# 05io.net
KiCad netlist of a schematic drawn in Altium Designer
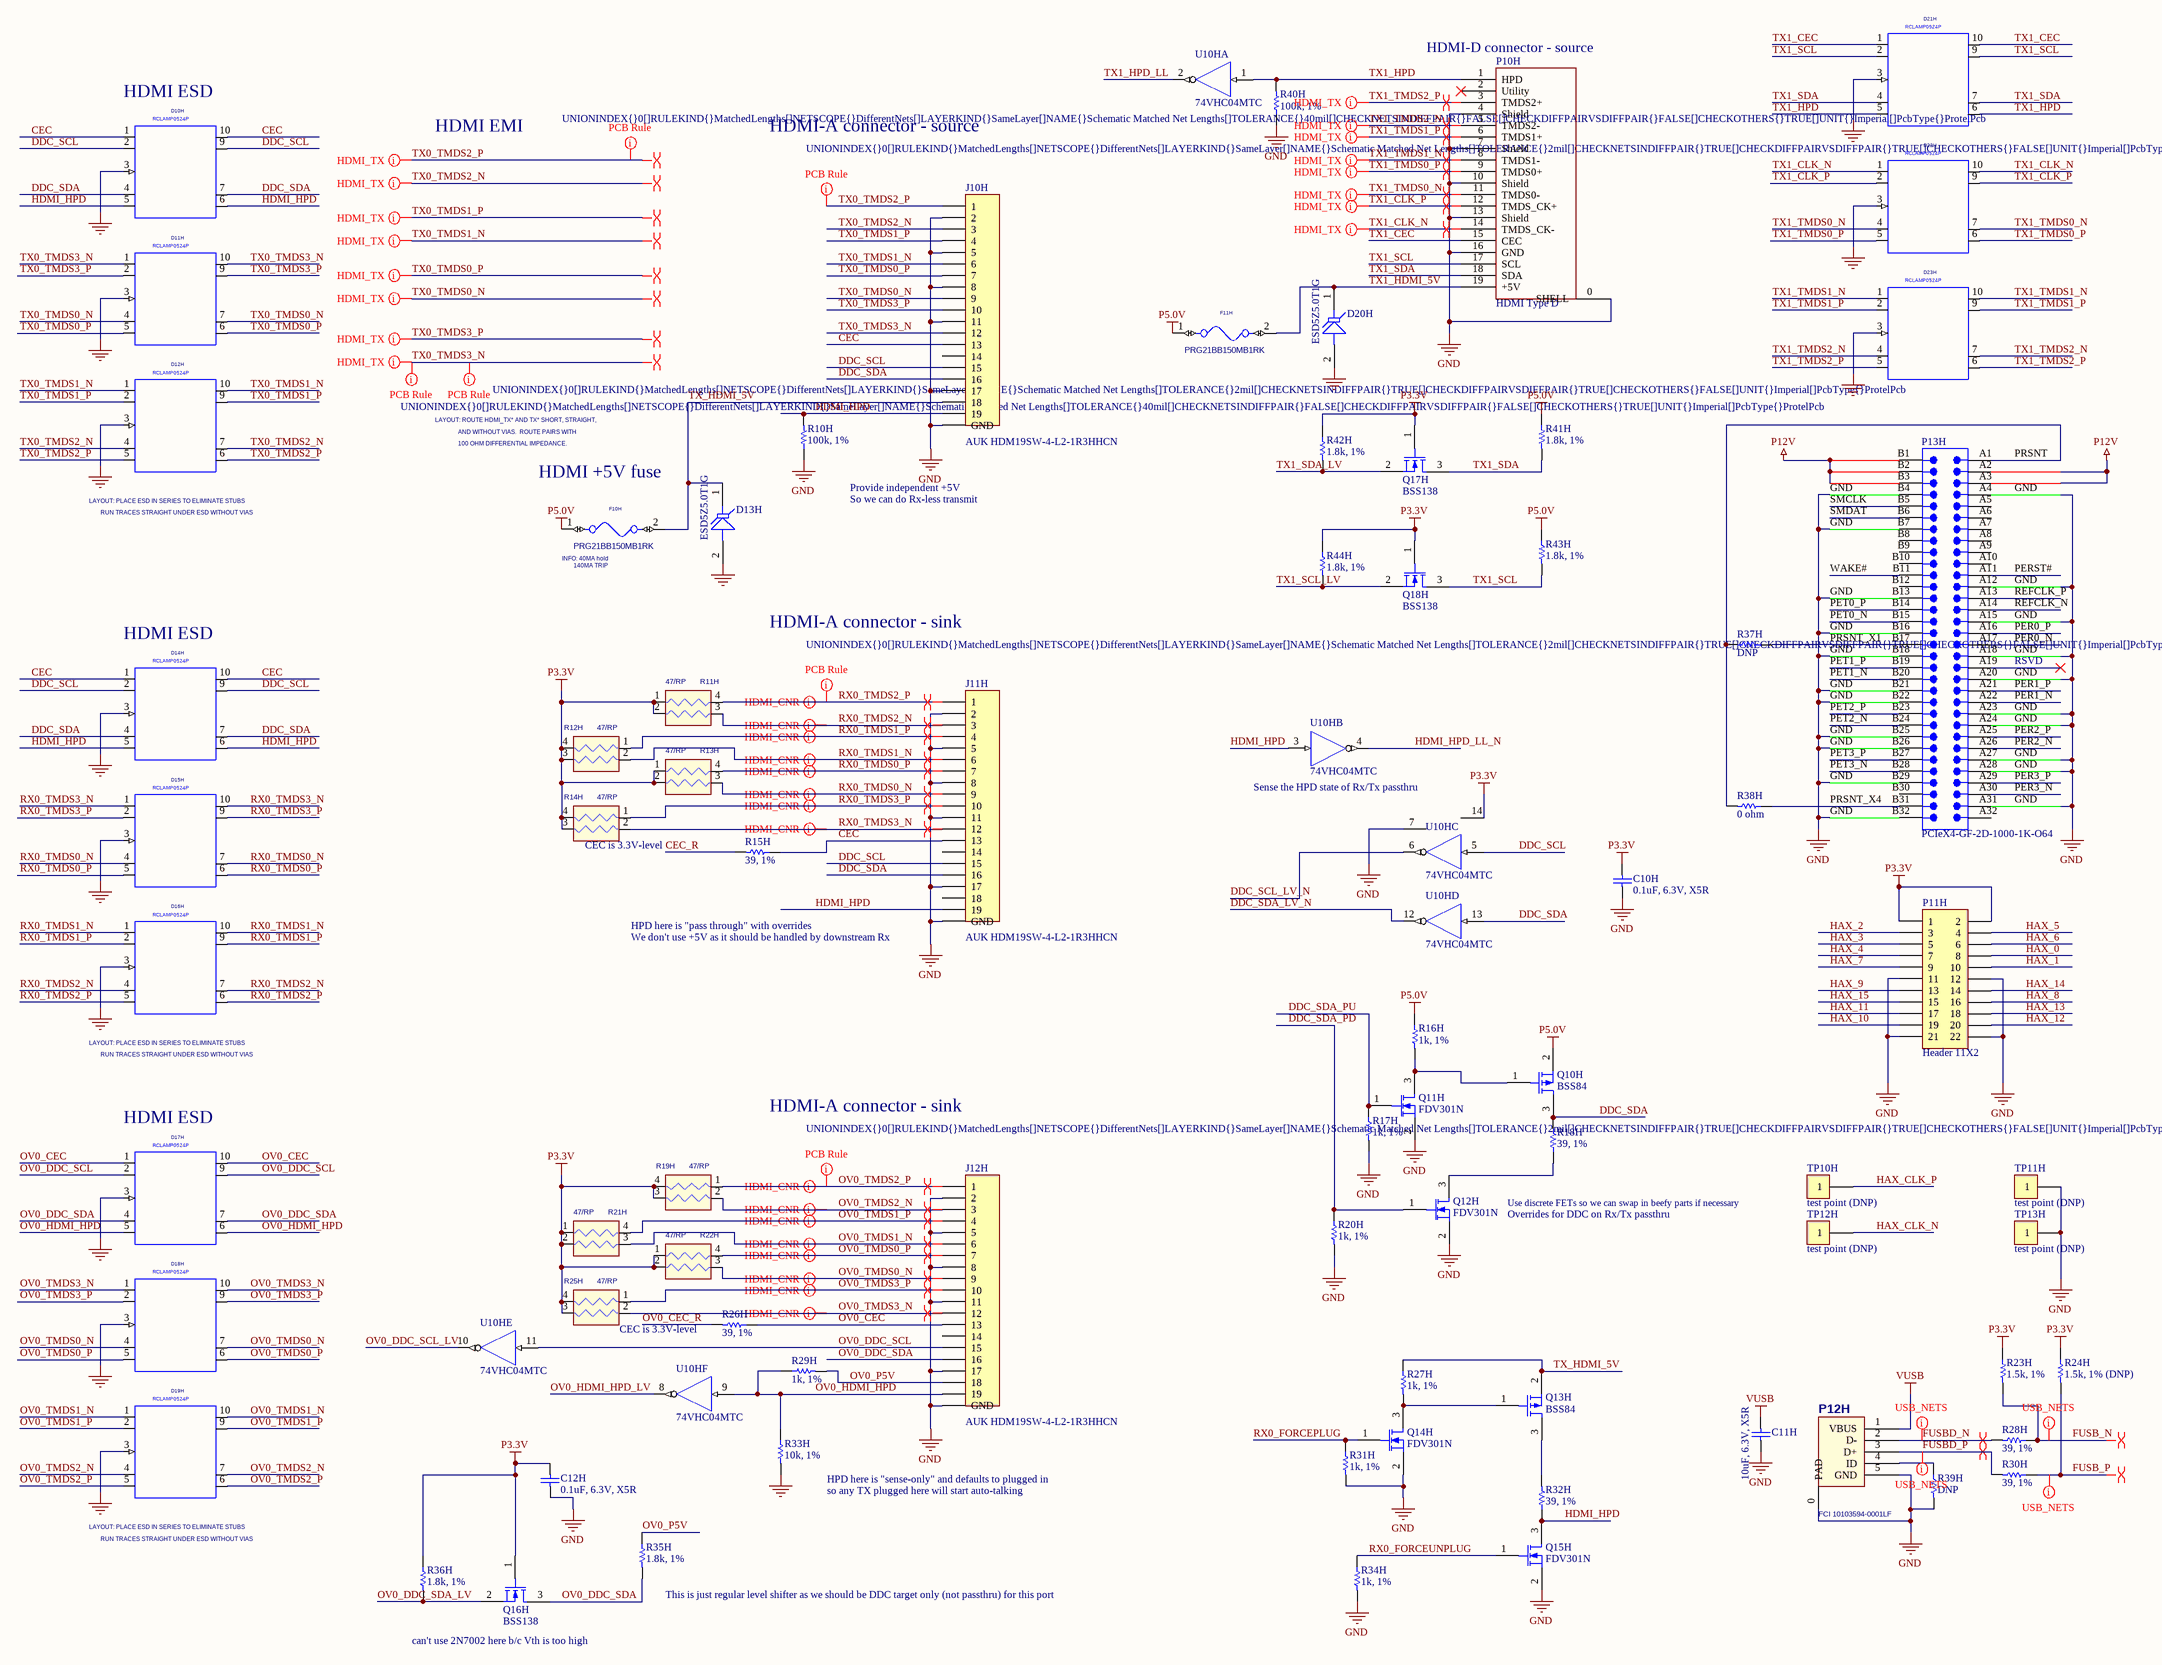
[diagram p0: 05io.SchDoc]

(export (version "E")
  (design (tool "Eeschema 10.0.6"))
  (components
    (comp (ref "C10H")
      (value "0.1uF, 6.3V, X5R")
      (footprint "CAPC0603X03L")
      (description "Capacitor (Semiconductor SIM Model)")
      (fields (field (name "MPN") "CL03A104KQ3NNNC"))
      (libsource (lib "Miscellaneous Devices") (part "Cap Semi"))
    )
    (comp (ref "C11H")
      (value "10uF, 6.3V, X5R")
      (footprint "CAPC1608N")
      (description "Capacitor (Semiconductor SIM Model)")
      (fields (field (name "MPN") "CL10A106MQ8NNNC"))
      (libsource (lib "Miscellaneous Devices") (part "Cap Semi"))
    )
    (comp (ref "C12H")
      (value "0.1uF, 6.3V, X5R")
      (footprint "CAPC0603X03L")
      (description "Capacitor (Semiconductor SIM Model)")
      (fields (field (name "MPN") "CL03A104KQ3NNNC"))
      (libsource (lib "Miscellaneous Devices") (part "Cap Semi"))
    )
    (comp (ref "D10H")
      (value "RCLAMP0524P")
      (fields (field (name "PART_NUMBER") "V00004-001") (field (name "MPN") "RCLAMP0524PATCT"))
      (libsource (lib "*") (part "RCLAMP0524P"))
    )
    (comp (ref "D11H")
      (value "RCLAMP0524P")
      (fields (field (name "PART_NUMBER") "V00004-001") (field (name "MPN") "RCLAMP0524PATCT"))
      (libsource (lib "*") (part "RCLAMP0524P"))
    )
    (comp (ref "D12H")
      (value "RCLAMP0524P")
      (fields (field (name "PART_NUMBER") "V00004-001") (field (name "MPN") "RCLAMP0524PATCT"))
      (libsource (lib "*") (part "RCLAMP0524P"))
    )
    (comp (ref "D13H")
      (value "ESD5Z5.0T1G")
      (footprint "SOD-523")
      (description "On Semi 5.0V standoff TVS diode")
      (fields (field (name "PUBLISHER") "Altium Limited"))
      (libsource (lib "Miscellaneous Devices") (part "Tranzorb"))
    )
    (comp (ref "D14H")
      (value "RCLAMP0524P")
      (fields (field (name "PART_NUMBER") "V00004-001") (field (name "MPN") "RCLAMP0524PATCT"))
      (libsource (lib "*") (part "RCLAMP0524P"))
    )
    (comp (ref "D15H")
      (value "RCLAMP0524P")
      (fields (field (name "PART_NUMBER") "V00004-001") (field (name "MPN") "RCLAMP0524PATCT"))
      (libsource (lib "*") (part "RCLAMP0524P"))
    )
    (comp (ref "D16H")
      (value "RCLAMP0524P")
      (fields (field (name "PART_NUMBER") "V00004-001") (field (name "MPN") "RCLAMP0524PATCT"))
      (libsource (lib "*") (part "RCLAMP0524P"))
    )
    (comp (ref "D17H")
      (value "RCLAMP0524P")
      (fields (field (name "PART_NUMBER") "V00004-001") (field (name "MPN") "RCLAMP0524PATCT"))
      (libsource (lib "*") (part "RCLAMP0524P"))
    )
    (comp (ref "D18H")
      (value "RCLAMP0524P")
      (fields (field (name "PART_NUMBER") "V00004-001") (field (name "MPN") "RCLAMP0524PATCT"))
      (libsource (lib "*") (part "RCLAMP0524P"))
    )
    (comp (ref "D19H")
      (value "RCLAMP0524P")
      (fields (field (name "PART_NUMBER") "V00004-001") (field (name "MPN") "RCLAMP0524PATCT"))
      (libsource (lib "*") (part "RCLAMP0524P"))
    )
    (comp (ref "D20H")
      (value "ESD5Z5.0T1G")
      (footprint "SOD-523")
      (description "On Semi 5.0V standoff TVS diode")
      (fields (field (name "PUBLISHER") "Altium Limited"))
      (libsource (lib "Miscellaneous Devices") (part "Tranzorb"))
    )
    (comp (ref "D21H")
      (value "RCLAMP0524P")
      (fields (field (name "PART_NUMBER") "V00004-001") (field (name "MPN") "RCLAMP0524PATCT"))
      (libsource (lib "*") (part "RCLAMP0524P"))
    )
    (comp (ref "D22H")
      (value "RCLAMP0524P")
      (fields (field (name "PART_NUMBER") "V00004-001") (field (name "MPN") "RCLAMP0524PATCT"))
      (libsource (lib "*") (part "RCLAMP0524P"))
    )
    (comp (ref "D23H")
      (value "RCLAMP0524P")
      (fields (field (name "PART_NUMBER") "V00004-001") (field (name "MPN") "RCLAMP0524PATCT"))
      (libsource (lib "*") (part "RCLAMP0524P"))
    )
    (comp (ref "F10H")
      (value "PRG21BB150MB1RK")
      (description "Murata 140mA fuse, 40mA hold")
      (fields (field (name "PART_NUMBER") "M00014-001"))
      (libsource (lib "*") (part "FUSE0805"))
    )
    (comp (ref "F11H")
      (value "PRG21BB150MB1RK")
      (description "Murata 140mA fuse, 40mA hold")
      (fields (field (name "PART_NUMBER") "M00014-001"))
      (libsource (lib "*") (part "FUSE0805"))
    )
    (comp (ref "J10H")
      (value "AUK HDM19SW-4-L2-1R3HHCN")
      (footprint "MOLEX_47151-0001")
      (description "Molex HDMI connector, Type A")
      (fields (field (name "MPN") "HDM19SW-4-L2-1R3HHCN") (field (name "PUBLISHER") "Altium Limited"))
      (libsource (lib "Miscellaneous Connectors") (part "Header 19"))
    )
    (comp (ref "J11H")
      (value "AUK HDM19SW-4-L2-1R3HHCN")
      (footprint "MOLEX_47151-0001")
      (description "Molex HDMI connector, Type A")
      (fields (field (name "MPN") "HDM19SW-4-L2-1R3HHCN") (field (name "PUBLISHER") "Altium Limited"))
      (libsource (lib "Miscellaneous Connectors") (part "Header 19"))
    )
    (comp (ref "J12H")
      (value "AUK HDM19SW-4-L2-1R3HHCN")
      (footprint "MOLEX_47151-0001")
      (description "Molex HDMI connector, Type A")
      (fields (field (name "MPN") "HDM19SW-4-L2-1R3HHCN") (field (name "PUBLISHER") "Altium Limited"))
      (libsource (lib "Miscellaneous Connectors") (part "Header 19"))
    )
    (comp (ref "P10H")
      (value "HDMI Type D")
      (footprint "MOLEX_0467651301")
      (description "HDMI Type D with through-hole mounts")
      (fields (field (name "MPN") "0467651301"))
      (libsource (lib "commonsch-new") (part "HDMI-TYPE-D"))
    )
    (comp (ref "P11H")
      (value "Header 11X2")
      (footprint "HDR2X11")
      (description "Header, 11-Pin, Dual row")
      (fields (field (name "PUBLISHER") "Altium Limited"))
      (libsource (lib "Miscellaneous Connectors") (part "Header 11X2"))
    )
    (comp (ref "P12H")
      (value "FCI 10103594-0001LF")
      (footprint "USB_MICRO_B_SMT")
      (description "Micro USB B type connector")
      (fields (field (name "MPN") "10103594-0001LF"))
      (libsource (lib "*") (part "USB_MINI-AB_1"))
    )
    (comp (ref "P13H")
      (value "PCIeX4-GF-2D-1000-1K-O64")
      (footprint "PCIeX4-GF-2D-1000-1K-O64")
      (description "Golden finger, PCIeX4, Dual, Opposite, Pitch 1mm, 64-Position")
      (fields (field (name "PUBLISHER") "Altium"))
      (libsource (lib "altium-import") (part "root_3_CMP-0001-00031-1_"))
    )
    (comp (ref "Q10H")
      (value "BSS84")
      (footprint "SOT23-3N")
      (description "P-Channel MOSFET")
      (fields (field (name "PUBLISHER") "Altium Limited"))
      (libsource (lib "Miscellaneous Devices") (part "MOSFET-P"))
    )
    (comp (ref "Q11H")
      (value "FDV301N")
      (footprint "SOT23-3N")
      (description "N-Channel MOSFET")
      (fields (field (name "PUBLISHER") "Altium Limited"))
      (libsource (lib "Miscellaneous Devices") (part "MOSFET-N"))
    )
    (comp (ref "Q12H")
      (value "FDV301N")
      (footprint "SOT23-3N")
      (description "N-Channel MOSFET")
      (fields (field (name "PUBLISHER") "Altium Limited"))
      (libsource (lib "Miscellaneous Devices") (part "MOSFET-N"))
    )
    (comp (ref "Q13H")
      (value "BSS84")
      (footprint "SOT23-3N")
      (description "P-Channel MOSFET")
      (fields (field (name "PUBLISHER") "Altium Limited"))
      (libsource (lib "Miscellaneous Devices") (part "MOSFET-P"))
    )
    (comp (ref "Q14H")
      (value "FDV301N")
      (footprint "SOT23-3N")
      (description "N-Channel MOSFET")
      (fields (field (name "PUBLISHER") "Altium Limited"))
      (libsource (lib "Miscellaneous Devices") (part "MOSFET-N"))
    )
    (comp (ref "Q15H")
      (value "FDV301N")
      (footprint "SOT23-3N")
      (description "N-Channel MOSFET")
      (fields (field (name "PUBLISHER") "Altium Limited"))
      (libsource (lib "Miscellaneous Devices") (part "MOSFET-N"))
    )
    (comp (ref "Q16H")
      (value "BSS138")
      (footprint "SOT23-3N")
      (description "N-Channel MOSFET")
      (fields (field (name "MPN") "BSS138LT1G") (field (name "PUBLISHER") "Altium Limited"))
      (libsource (lib "Miscellaneous Devices") (part "MOSFET-N"))
    )
    (comp (ref "Q17H")
      (value "BSS138")
      (footprint "SOT23-3N")
      (description "N-Channel MOSFET")
      (fields (field (name "MPN") "BSS138LT1G") (field (name "PUBLISHER") "Altium Limited"))
      (libsource (lib "Miscellaneous Devices") (part "MOSFET-N"))
    )
    (comp (ref "Q18H")
      (value "BSS138")
      (footprint "SOT23-3N")
      (description "N-Channel MOSFET")
      (fields (field (name "MPN") "BSS138LT1G") (field (name "PUBLISHER") "Altium Limited"))
      (libsource (lib "Miscellaneous Devices") (part "MOSFET-N"))
    )
    (comp (ref "R10H")
      (value "100k, 1%")
      (footprint "RESC1005N")
      (description "Resistor")
      (fields (field (name "MPN") "ANY"))
      (libsource (lib "Miscellaneous Devices") (part "Res1"))
    )
    (comp (ref "R11H")
      (value "47/RP")
      (fields (field (name "MPN") "RP102PJ470CS") (field (name "MFG") "SAMSUNG"))
      (libsource (lib "") (part "RPACK2_1"))
    )
    (comp (ref "R12H")
      (value "47/RP")
      (fields (field (name "MPN") "RP102PJ470CS") (field (name "MFG") "SAMSUNG"))
      (libsource (lib "*") (part "RPACK2"))
    )
    (comp (ref "R13H")
      (value "47/RP")
      (fields (field (name "MPN") "RP102PJ470CS") (field (name "MFG") "SAMSUNG"))
      (libsource (lib "") (part "RPACK2_1"))
    )
    (comp (ref "R14H")
      (value "47/RP")
      (fields (field (name "MPN") "RP102PJ470CS") (field (name "MFG") "SAMSUNG"))
      (libsource (lib "*") (part "RPACK2"))
    )
    (comp (ref "R15H")
      (value "39, 1%")
      (footprint "RESC1005N")
      (description "Resistor")
      (fields (field (name "MPN") "ANY"))
      (libsource (lib "Miscellaneous Devices") (part "Res1"))
    )
    (comp (ref "R16H")
      (value "1k, 1%")
      (footprint "RESC1005N")
      (description "Resistor")
      (fields (field (name "MPN") "RS02U102FT"))
      (libsource (lib "Miscellaneous Devices") (part "Res1"))
    )
    (comp (ref "R17H")
      (value "1k, 1%")
      (footprint "RESC1005N")
      (description "Resistor")
      (fields (field (name "MPN") "RS02U102FT"))
      (libsource (lib "Miscellaneous Devices") (part "Res1"))
    )
    (comp (ref "R18H")
      (value "39, 1%")
      (footprint "RESC1005N")
      (description "Resistor")
      (fields (field (name "MPN") "ANY"))
      (libsource (lib "Miscellaneous Devices") (part "Res1"))
    )
    (comp (ref "R19H")
      (value "47/RP")
      (fields (field (name "MPN") "RP102PJ470CS") (field (name "MFG") "SAMSUNG"))
      (libsource (lib "*") (part "RPACK2"))
    )
    (comp (ref "R20H")
      (value "1k, 1%")
      (footprint "RESC1005N")
      (description "Resistor")
      (fields (field (name "MPN") "RS02U102FT"))
      (libsource (lib "Miscellaneous Devices") (part "Res1"))
    )
    (comp (ref "R21H")
      (value "47/RP")
      (fields (field (name "MPN") "RP102PJ470CS") (field (name "MFG") "SAMSUNG"))
      (libsource (lib "") (part "RPACK2_1"))
    )
    (comp (ref "R22H")
      (value "47/RP")
      (fields (field (name "MPN") "RP102PJ470CS") (field (name "MFG") "SAMSUNG"))
      (libsource (lib "") (part "RPACK2_1"))
    )
    (comp (ref "R23H")
      (value "1.5k, 1%")
      (footprint "RESC1005N")
      (description "Resistor")
      (fields (field (name "MPN") "RS02U152FT"))
      (libsource (lib "Miscellaneous Devices") (part "Res1"))
    )
    (comp (ref "R24H")
      (value "1.5k, 1% (DNP)")
      (footprint "RESC1005N")
      (description "Resistor")
      (fields (field (name "MPN") "DNP"))
      (libsource (lib "Miscellaneous Devices") (part "Res1"))
    )
    (comp (ref "R25H")
      (value "47/RP")
      (fields (field (name "MPN") "RP102PJ470CS") (field (name "MFG") "SAMSUNG"))
      (libsource (lib "*") (part "RPACK2"))
    )
    (comp (ref "R26H")
      (value "39, 1%")
      (footprint "RESC1005N")
      (description "Resistor")
      (fields (field (name "MPN") "ANY"))
      (libsource (lib "Miscellaneous Devices") (part "Res1"))
    )
    (comp (ref "R27H")
      (value "1k, 1%")
      (footprint "RESC1005N")
      (description "Resistor")
      (fields (field (name "MPN") "RS02U102FT"))
      (libsource (lib "Miscellaneous Devices") (part "Res1"))
    )
    (comp (ref "R28H")
      (value "39, 1%")
      (footprint "RESC1005N")
      (description "Resistor")
      (fields (field (name "MPN") "ANY"))
      (libsource (lib "Miscellaneous Devices") (part "Res1"))
    )
    (comp (ref "R29H")
      (value "1k, 1%")
      (footprint "RESC1005N")
      (description "Resistor")
      (fields (field (name "MPN") "RS02U102FT"))
      (libsource (lib "Miscellaneous Devices") (part "Res1"))
    )
    (comp (ref "R30H")
      (value "39, 1%")
      (footprint "RESC1005N")
      (description "Resistor")
      (fields (field (name "MPN") "ANY"))
      (libsource (lib "Miscellaneous Devices") (part "Res1"))
    )
    (comp (ref "R31H")
      (value "1k, 1%")
      (footprint "RESC1005N")
      (description "Resistor")
      (fields (field (name "MPN") "RS02U102FT"))
      (libsource (lib "Miscellaneous Devices") (part "Res1"))
    )
    (comp (ref "R32H")
      (value "39, 1%")
      (footprint "RESC1005N")
      (description "Resistor")
      (fields (field (name "MPN") "ANY"))
      (libsource (lib "Miscellaneous Devices") (part "Res1"))
    )
    (comp (ref "R33H")
      (value "10k, 1%")
      (footprint "RESC1005N")
      (description "Resistor")
      (fields (field (name "MPN") "RS02U103FT"))
      (libsource (lib "Miscellaneous Devices") (part "Res1"))
    )
    (comp (ref "R34H")
      (value "1k, 1%")
      (footprint "RESC1005N")
      (description "Resistor")
      (fields (field (name "MPN") "RS02U102FT"))
      (libsource (lib "Miscellaneous Devices") (part "Res1"))
    )
    (comp (ref "R35H")
      (value "1.8k, 1%")
      (footprint "RESC1005N")
      (description "Resistor")
      (fields (field (name "MPN") "RS02U182FT") (field (name "PUBLISHER") "Altium Limited"))
      (libsource (lib "Miscellaneous Devices") (part "Res1"))
    )
    (comp (ref "R36H")
      (value "1.8k, 1%")
      (footprint "RESC1005N")
      (description "Resistor")
      (fields (field (name "MPN") "RS02U182FT") (field (name "PUBLISHER") "Altium Limited"))
      (libsource (lib "Miscellaneous Devices") (part "Res1"))
    )
    (comp (ref "R37H")
      (value "DNP")
      (footprint "RESC1005N")
      (description "Resistor")
      (fields (field (name "MPN") "ANY"))
      (libsource (lib "Miscellaneous Devices") (part "Res1"))
    )
    (comp (ref "R38H")
      (value "0 ohm")
      (footprint "RESC1005N")
      (description "Resistor")
      (fields (field (name "MPN") "ANY"))
      (libsource (lib "Miscellaneous Devices") (part "Res1"))
    )
    (comp (ref "R39H")
      (value "DNP")
      (footprint "RESC1005N")
      (description "Resistor")
      (fields (field (name "MPN") "ANY"))
      (libsource (lib "Miscellaneous Devices") (part "Res1"))
    )
    (comp (ref "R40H")
      (value "100k, 1%")
      (footprint "RESC1005N")
      (description "Resistor")
      (fields (field (name "MPN") "ANY"))
      (libsource (lib "Miscellaneous Devices") (part "Res1"))
    )
    (comp (ref "R41H")
      (value "1.8k, 1%")
      (footprint "RESC1005N")
      (description "Resistor")
      (fields (field (name "MPN") "RS02U182FT") (field (name "PUBLISHER") "Altium Limited"))
      (libsource (lib "Miscellaneous Devices") (part "Res1"))
    )
    (comp (ref "R42H")
      (value "1.8k, 1%")
      (footprint "RESC1005N")
      (description "Resistor")
      (fields (field (name "MPN") "RS02U182FT") (field (name "PUBLISHER") "Altium Limited"))
      (libsource (lib "Miscellaneous Devices") (part "Res1"))
    )
    (comp (ref "R43H")
      (value "1.8k, 1%")
      (footprint "RESC1005N")
      (description "Resistor")
      (fields (field (name "MPN") "RS02U182FT") (field (name "PUBLISHER") "Altium Limited"))
      (libsource (lib "Miscellaneous Devices") (part "Res1"))
    )
    (comp (ref "R44H")
      (value "1.8k, 1%")
      (footprint "RESC1005N")
      (description "Resistor")
      (fields (field (name "MPN") "RS02U182FT") (field (name "PUBLISHER") "Altium Limited"))
      (libsource (lib "Miscellaneous Devices") (part "Res1"))
    )
    (comp (ref "TP10H")
      (value "test point (DNP)")
      (footprint "TP_2MM_SQ")
      (description "Connector")
      (libsource (lib "*") (part "CON1"))
    )
    (comp (ref "TP11H")
      (value "test point (DNP)")
      (footprint "TP_2MM_SQ")
      (description "Connector")
      (libsource (lib "*") (part "CON1"))
    )
    (comp (ref "TP12H")
      (value "test point (DNP)")
      (footprint "TP_2MM_SQ")
      (description "Connector")
      (libsource (lib "*") (part "CON1"))
    )
    (comp (ref "TP13H")
      (value "test point (DNP)")
      (footprint "TP_2MM_SQ")
      (description "Connector")
      (libsource (lib "*") (part "CON1"))
    )
    (comp (ref "U10H")
      (value "74VHC04MTC")
      (footprint "TSOP65P640-14AN")
      (description "Hex Inverter, 14-Pin SOIC, Commercial Grade")
      (fields (field (name "MPN") "74VHC04MTCX") (field (name "PUBLISHER") "Altium Limited"))
      (libsource (lib "FSC Logic Gate") (part "74AC04SC"))
    )
  )
  (nets
    (net (code "1") (name "/CEC") (class "Default")
      (node (ref "D10H") (pin "1") (pinfunction "IO1A_1") (pintype "bidirectional"))
      (node (ref "D10H") (pin "10") (pinfunction "IO1B_10") (pintype "bidirectional"))
      (node (ref "D14H") (pin "1") (pinfunction "IO1A_1") (pintype "bidirectional"))
      (node (ref "D14H") (pin "10") (pinfunction "IO1B_10") (pintype "bidirectional"))
      (node (ref "J10H") (pin "13") (pinfunction "13_13") (pintype "passive"))
      (node (ref "J11H") (pin "13") (pinfunction "13_13") (pintype "passive"))
      (node (ref "R15H") (pin "1") (pinfunction "1_1") (pintype "passive"))
    )
    (net (code "2") (name "/CEC_R") (class "Default")
      (node (ref "R15H") (pin "2") (pinfunction "2_2") (pintype "passive"))
    )
    (net (code "3") (name "/DDC_SCL") (class "Default")
      (node (ref "D10H") (pin "2") (pinfunction "IO2A_2") (pintype "bidirectional"))
      (node (ref "D10H") (pin "9") (pinfunction "IO2B_9") (pintype "bidirectional"))
      (node (ref "D14H") (pin "2") (pinfunction "IO2A_2") (pintype "bidirectional"))
      (node (ref "D14H") (pin "9") (pinfunction "IO2B_9") (pintype "bidirectional"))
      (node (ref "J10H") (pin "15") (pinfunction "15_15") (pintype "passive"))
      (node (ref "J11H") (pin "15") (pinfunction "15_15") (pintype "passive"))
      (node (ref "U10H") (pin "5") (pinfunction "A_5") (pintype "input"))
    )
    (net (code "4") (name "/DDC_SCL_LV_N") (class "Default")
      (node (ref "U10H") (pin "6") (pinfunction "~{O}_6") (pintype "output"))
    )
    (net (code "5") (name "/DDC_SDA") (class "Default")
      (node (ref "D10H") (pin "4") (pinfunction "IO3A_4") (pintype "bidirectional"))
      (node (ref "D10H") (pin "7") (pinfunction "IO3B_7") (pintype "bidirectional"))
      (node (ref "D14H") (pin "4") (pinfunction "IO3A_4") (pintype "bidirectional"))
      (node (ref "D14H") (pin "7") (pinfunction "IO3B_7") (pintype "bidirectional"))
      (node (ref "J10H") (pin "16") (pinfunction "16_16") (pintype "passive"))
      (node (ref "J11H") (pin "16") (pinfunction "16_16") (pintype "passive"))
      (node (ref "Q10H") (pin "3") (pinfunction "D_3") (pintype "passive"))
      (node (ref "R18H") (pin "2") (pinfunction "2_2") (pintype "passive"))
      (node (ref "U10H") (pin "13") (pinfunction "A_13") (pintype "input"))
    )
    (net (code "6") (name "/DDC_SDA_LV_N") (class "Default")
      (node (ref "U10H") (pin "12") (pinfunction "~{O}_12") (pintype "output"))
    )
    (net (code "7") (name "/DDC_SDA_PD") (class "Default")
      (node (ref "Q12H") (pin "1") (pinfunction "G_1") (pintype "passive"))
      (node (ref "R20H") (pin "1") (pinfunction "1_1") (pintype "passive"))
    )
    (net (code "8") (name "/DDC_SDA_PU") (class "Default")
      (node (ref "Q11H") (pin "1") (pinfunction "G_1") (pintype "passive"))
      (node (ref "R17H") (pin "1") (pinfunction "1_1") (pintype "passive"))
    )
    (net (code "9") (name "/FUSBD_N") (class "Default")
      (node (ref "P12H") (pin "2") (pinfunction "D-_2") (pintype "passive"))
      (node (ref "R28H") (pin "2") (pinfunction "2_2") (pintype "passive"))
    )
    (net (code "10") (name "/FUSBD_P") (class "Default")
      (node (ref "P12H") (pin "3") (pinfunction "D+_3") (pintype "passive"))
      (node (ref "R30H") (pin "2") (pinfunction "2_2") (pintype "passive"))
    )
    (net (code "11") (name "/FUSB_N") (class "Default")
      (node (ref "R23H") (pin "2") (pinfunction "2_2") (pintype "passive"))
      (node (ref "R28H") (pin "1") (pinfunction "1_1") (pintype "passive"))
    )
    (net (code "12") (name "/FUSB_P") (class "Default")
      (node (ref "R24H") (pin "2") (pinfunction "2_2") (pintype "passive"))
      (node (ref "R30H") (pin "1") (pinfunction "1_1") (pintype "passive"))
    )
    (net (code "13") (name "/HAX_0") (class "Default")
      (node (ref "P11H") (pin "8") (pinfunction "8_8") (pintype "passive"))
    )
    (net (code "14") (name "/HAX_1") (class "Default")
      (node (ref "P11H") (pin "10") (pinfunction "10_10") (pintype "passive"))
    )
    (net (code "15") (name "/HAX_2") (class "Default")
      (node (ref "P11H") (pin "3") (pinfunction "3_3") (pintype "passive"))
    )
    (net (code "16") (name "/HAX_3") (class "Default")
      (node (ref "P11H") (pin "5") (pinfunction "5_5") (pintype "passive"))
    )
    (net (code "17") (name "/HAX_4") (class "Default")
      (node (ref "P11H") (pin "7") (pinfunction "7_7") (pintype "passive"))
    )
    (net (code "18") (name "/HAX_5") (class "Default")
      (node (ref "P11H") (pin "4") (pinfunction "4_4") (pintype "passive"))
    )
    (net (code "19") (name "/HAX_6") (class "Default")
      (node (ref "P11H") (pin "6") (pinfunction "6_6") (pintype "passive"))
    )
    (net (code "20") (name "/HAX_7") (class "Default")
      (node (ref "P11H") (pin "9") (pinfunction "9_9") (pintype "passive"))
    )
    (net (code "21") (name "/HAX_8") (class "Default")
      (node (ref "P11H") (pin "16") (pinfunction "16_16") (pintype "passive"))
    )
    (net (code "22") (name "/HAX_9") (class "Default")
      (node (ref "P11H") (pin "13") (pinfunction "13_13") (pintype "passive"))
    )
    (net (code "23") (name "/HAX_10") (class "Default")
      (node (ref "P11H") (pin "19") (pinfunction "19_19") (pintype "passive"))
    )
    (net (code "24") (name "/HAX_11") (class "Default")
      (node (ref "P11H") (pin "17") (pinfunction "17_17") (pintype "passive"))
    )
    (net (code "25") (name "/HAX_12") (class "Default")
      (node (ref "P11H") (pin "20") (pinfunction "20_20") (pintype "passive"))
    )
    (net (code "26") (name "/HAX_13") (class "Default")
      (node (ref "P11H") (pin "18") (pinfunction "18_18") (pintype "passive"))
    )
    (net (code "27") (name "/HAX_14") (class "Default")
      (node (ref "P11H") (pin "14") (pinfunction "14_14") (pintype "passive"))
    )
    (net (code "28") (name "/HAX_15") (class "Default")
      (node (ref "P11H") (pin "15") (pinfunction "15_15") (pintype "passive"))
    )
    (net (code "29") (name "/HAX_CLK_N") (class "Default")
      (node (ref "TP12H") (pin "1") (pinfunction "1_1") (pintype "passive"))
    )
    (net (code "30") (name "/HAX_CLK_P") (class "Default")
      (node (ref "TP10H") (pin "1") (pinfunction "1_1") (pintype "passive"))
    )
    (net (code "31") (name "/HDMI_HPD") (class "Default")
      (node (ref "D10H") (pin "5") (pinfunction "IO4A_5") (pintype "bidirectional"))
      (node (ref "D10H") (pin "6") (pinfunction "IO4B_6") (pintype "bidirectional"))
      (node (ref "D14H") (pin "5") (pinfunction "IO4A_5") (pintype "bidirectional"))
      (node (ref "D14H") (pin "6") (pinfunction "IO4B_6") (pintype "bidirectional"))
      (node (ref "J10H") (pin "19") (pinfunction "19_19") (pintype "passive"))
      (node (ref "J11H") (pin "19") (pinfunction "19_19") (pintype "passive"))
      (node (ref "Q15H") (pin "3") (pinfunction "D_3") (pintype "passive"))
      (node (ref "R10H") (pin "2") (pinfunction "2_2") (pintype "passive"))
      (node (ref "R32H") (pin "1") (pinfunction "1_1") (pintype "passive"))
      (node (ref "U10H") (pin "3") (pinfunction "A_3") (pintype "input"))
    )
    (net (code "32") (name "/HDMI_HPD_LL_N") (class "Default")
      (node (ref "U10H") (pin "4") (pinfunction "~{O}_4") (pintype "output"))
    )
    (net (code "33") (name "/OV0_CEC") (class "Default")
      (node (ref "D17H") (pin "1") (pinfunction "IO1A_1") (pintype "bidirectional"))
      (node (ref "D17H") (pin "10") (pinfunction "IO1B_10") (pintype "bidirectional"))
      (node (ref "J12H") (pin "13") (pinfunction "13_13") (pintype "passive"))
      (node (ref "R26H") (pin "1") (pinfunction "1_1") (pintype "passive"))
    )
    (net (code "34") (name "/OV0_CEC_R") (class "Default")
      (node (ref "R26H") (pin "2") (pinfunction "2_2") (pintype "passive"))
    )
    (net (code "35") (name "/OV0_DDC_SCL") (class "Default")
      (node (ref "D17H") (pin "2") (pinfunction "IO2A_2") (pintype "bidirectional"))
      (node (ref "D17H") (pin "9") (pinfunction "IO2B_9") (pintype "bidirectional"))
      (node (ref "J12H") (pin "15") (pinfunction "15_15") (pintype "passive"))
      (node (ref "U10H") (pin "11") (pinfunction "A_11") (pintype "input"))
    )
    (net (code "36") (name "/OV0_DDC_SCL_LV") (class "Default")
      (node (ref "U10H") (pin "10") (pinfunction "~{O}_10") (pintype "output"))
    )
    (net (code "37") (name "/OV0_DDC_SDA") (class "Default")
      (node (ref "D17H") (pin "4") (pinfunction "IO3A_4") (pintype "bidirectional"))
      (node (ref "D17H") (pin "7") (pinfunction "IO3B_7") (pintype "bidirectional"))
      (node (ref "J12H") (pin "16") (pinfunction "16_16") (pintype "passive"))
      (node (ref "Q16H") (pin "3") (pinfunction "D_3") (pintype "passive"))
      (node (ref "R35H") (pin "2") (pinfunction "2_2") (pintype "passive"))
    )
    (net (code "38") (name "/OV0_DDC_SDA_LV") (class "Default")
      (node (ref "Q16H") (pin "2") (pinfunction "S_2") (pintype "passive"))
      (node (ref "R36H") (pin "2") (pinfunction "2_2") (pintype "passive"))
    )
    (net (code "39") (name "/OV0_HDMI_HPD") (class "Default")
      (node (ref "D17H") (pin "5") (pinfunction "IO4A_5") (pintype "bidirectional"))
      (node (ref "D17H") (pin "6") (pinfunction "IO4B_6") (pintype "bidirectional"))
      (node (ref "J12H") (pin "19") (pinfunction "19_19") (pintype "passive"))
      (node (ref "R29H") (pin "1") (pinfunction "1_1") (pintype "passive"))
      (node (ref "R33H") (pin "1") (pinfunction "1_1") (pintype "passive"))
      (node (ref "U10H") (pin "9") (pinfunction "A_9") (pintype "input"))
    )
    (net (code "40") (name "/OV0_HDMI_HPD_LV") (class "Default")
      (node (ref "U10H") (pin "8") (pinfunction "~{O}_8") (pintype "output"))
    )
    (net (code "41") (name "/OV0_P5V") (class "Default")
      (node (ref "J12H") (pin "18") (pinfunction "18_18") (pintype "passive"))
      (node (ref "R29H") (pin "2") (pinfunction "2_2") (pintype "passive"))
      (node (ref "R35H") (pin "1") (pinfunction "1_1") (pintype "passive"))
    )
    (net (code "42") (name "/OV0_TMDS0_N") (class "Default")
      (node (ref "D18H") (pin "4") (pinfunction "IO3A_4") (pintype "bidirectional"))
      (node (ref "D18H") (pin "7") (pinfunction "IO3B_7") (pintype "bidirectional"))
      (node (ref "J12H") (pin "9") (pinfunction "9_9") (pintype "passive"))
      (node (ref "R22H") (pin "3") (pinfunction "R22_3") (pintype "passive"))
    )
    (net (code "43") (name "/OV0_TMDS0_P") (class "Default")
      (node (ref "D18H") (pin "5") (pinfunction "IO4A_5") (pintype "bidirectional"))
      (node (ref "D18H") (pin "6") (pinfunction "IO4B_6") (pintype "bidirectional"))
      (node (ref "J12H") (pin "7") (pinfunction "7_7") (pintype "passive"))
      (node (ref "R22H") (pin "4") (pinfunction "R12_4") (pintype "passive"))
    )
    (net (code "44") (name "/OV0_TMDS1_N") (class "Default")
      (node (ref "D19H") (pin "1") (pinfunction "IO1A_1") (pintype "bidirectional"))
      (node (ref "D19H") (pin "10") (pinfunction "IO1B_10") (pintype "bidirectional"))
      (node (ref "J12H") (pin "6") (pinfunction "6_6") (pintype "passive"))
      (node (ref "R21H") (pin "3") (pinfunction "R22_3") (pintype "passive"))
    )
    (net (code "45") (name "/OV0_TMDS1_P") (class "Default")
      (node (ref "D19H") (pin "2") (pinfunction "IO2A_2") (pintype "bidirectional"))
      (node (ref "D19H") (pin "9") (pinfunction "IO2B_9") (pintype "bidirectional"))
      (node (ref "J12H") (pin "4") (pinfunction "4_4") (pintype "passive"))
      (node (ref "R21H") (pin "4") (pinfunction "R12_4") (pintype "passive"))
    )
    (net (code "46") (name "/OV0_TMDS2_N") (class "Default")
      (node (ref "D19H") (pin "4") (pinfunction "IO3A_4") (pintype "bidirectional"))
      (node (ref "D19H") (pin "7") (pinfunction "IO3B_7") (pintype "bidirectional"))
      (node (ref "J12H") (pin "3") (pinfunction "3_3") (pintype "passive"))
      (node (ref "R19H") (pin "2") (pinfunction "R2_2") (pintype "passive"))
    )
    (net (code "47") (name "/OV0_TMDS2_P") (class "Default")
      (node (ref "D19H") (pin "5") (pinfunction "IO4A_5") (pintype "bidirectional"))
      (node (ref "D19H") (pin "6") (pinfunction "IO4B_6") (pintype "bidirectional"))
      (node (ref "J12H") (pin "1") (pinfunction "1_1") (pintype "passive"))
      (node (ref "R19H") (pin "1") (pinfunction "R1_1") (pintype "passive"))
    )
    (net (code "48") (name "/OV0_TMDS3_N") (class "Default")
      (node (ref "D18H") (pin "1") (pinfunction "IO1A_1") (pintype "bidirectional"))
      (node (ref "D18H") (pin "10") (pinfunction "IO1B_10") (pintype "bidirectional"))
      (node (ref "J12H") (pin "12") (pinfunction "12_12") (pintype "passive"))
      (node (ref "R25H") (pin "2") (pinfunction "R2_2") (pintype "passive"))
    )
    (net (code "49") (name "/OV0_TMDS3_P") (class "Default")
      (node (ref "D18H") (pin "2") (pinfunction "IO2A_2") (pintype "bidirectional"))
      (node (ref "D18H") (pin "9") (pinfunction "IO2B_9") (pintype "bidirectional"))
      (node (ref "J12H") (pin "10") (pinfunction "10_10") (pintype "passive"))
      (node (ref "R25H") (pin "1") (pinfunction "R1_1") (pintype "passive"))
    )
    (net (code "50") (name "/PER0_N") (class "Default")
      (node (ref "P13H") (pin "A17") (pinfunction "A17_A17") (pintype "passive"))
    )
    (net (code "51") (name "/PER0_P") (class "Default")
      (node (ref "P13H") (pin "A16") (pinfunction "A16_A16") (pintype "passive"))
    )
    (net (code "52") (name "/PER1_N") (class "Default")
      (node (ref "P13H") (pin "A22") (pinfunction "A22_A22") (pintype "passive"))
    )
    (net (code "53") (name "/PER1_P") (class "Default")
      (node (ref "P13H") (pin "A21") (pinfunction "A21_A21") (pintype "passive"))
    )
    (net (code "54") (name "/PER2_N") (class "Default")
      (node (ref "P13H") (pin "A26") (pinfunction "A26_A26") (pintype "passive"))
    )
    (net (code "55") (name "/PER2_P") (class "Default")
      (node (ref "P13H") (pin "A25") (pinfunction "A25_A25") (pintype "passive"))
    )
    (net (code "56") (name "/PER3_N") (class "Default")
      (node (ref "P13H") (pin "A30") (pinfunction "A30_A30") (pintype "passive"))
    )
    (net (code "57") (name "/PER3_P") (class "Default")
      (node (ref "P13H") (pin "A29") (pinfunction "A29_A29") (pintype "passive"))
    )
    (net (code "58") (name "/PERST#") (class "Default")
      (node (ref "P13H") (pin "A11") (pinfunction "A11_A11") (pintype "passive"))
    )
    (net (code "59") (name "/PET0_N") (class "Default")
      (node (ref "P13H") (pin "B15") (pinfunction "B15_B15") (pintype "passive"))
    )
    (net (code "60") (name "/PET0_P") (class "Default")
      (node (ref "P13H") (pin "B14") (pinfunction "B14_B14") (pintype "passive"))
    )
    (net (code "61") (name "/PET1_N") (class "Default")
      (node (ref "P13H") (pin "B20") (pinfunction "B20_B20") (pintype "passive"))
    )
    (net (code "62") (name "/PET1_P") (class "Default")
      (node (ref "P13H") (pin "B19") (pinfunction "B19_B19") (pintype "passive"))
    )
    (net (code "63") (name "/PET2_N") (class "Default")
      (node (ref "P13H") (pin "B24") (pinfunction "B24_B24") (pintype "passive"))
    )
    (net (code "64") (name "/PET2_P") (class "Default")
      (node (ref "P13H") (pin "B23") (pinfunction "B23_B23") (pintype "passive"))
    )
    (net (code "65") (name "/PET3_N") (class "Default")
      (node (ref "P13H") (pin "B28") (pinfunction "B28_B28") (pintype "passive"))
    )
    (net (code "66") (name "/PET3_P") (class "Default")
      (node (ref "P13H") (pin "B27") (pinfunction "B27_B27") (pintype "passive"))
    )
    (net (code "67") (name "/PRSNT") (class "Default")
      (node (ref "P13H") (pin "A1") (pinfunction "A1_A1") (pintype "passive"))
      (node (ref "R37H") (pin "2") (pinfunction "2_2") (pintype "passive"))
      (node (ref "R38H") (pin "2") (pinfunction "2_2") (pintype "passive"))
    )
    (net (code "68") (name "/PRSNT_X1") (class "Default")
      (node (ref "P13H") (pin "B17") (pinfunction "B17_B17") (pintype "passive"))
      (node (ref "R37H") (pin "1") (pinfunction "1_1") (pintype "passive"))
    )
    (net (code "69") (name "/PRSNT_X4") (class "Default")
      (node (ref "P13H") (pin "B31") (pinfunction "B31_B31") (pintype "passive"))
      (node (ref "R38H") (pin "1") (pinfunction "1_1") (pintype "passive"))
    )
    (net (code "70") (name "/REFCLK_N") (class "Default")
      (node (ref "P13H") (pin "A14") (pinfunction "A14_A14") (pintype "passive"))
    )
    (net (code "71") (name "/REFCLK_P") (class "Default")
      (node (ref "P13H") (pin "A13") (pinfunction "A13_A13") (pintype "passive"))
    )
    (net (code "72") (name "/RX0_FORCEPLUG") (class "Default")
      (node (ref "Q14H") (pin "1") (pinfunction "G_1") (pintype "passive"))
      (node (ref "R31H") (pin "1") (pinfunction "1_1") (pintype "passive"))
    )
    (net (code "73") (name "/RX0_FORCEUNPLUG") (class "Default")
      (node (ref "Q15H") (pin "1") (pinfunction "G_1") (pintype "passive"))
      (node (ref "R34H") (pin "1") (pinfunction "1_1") (pintype "passive"))
    )
    (net (code "74") (name "/RX0_TMDS0_N") (class "Default")
      (node (ref "D15H") (pin "4") (pinfunction "IO3A_4") (pintype "bidirectional"))
      (node (ref "D15H") (pin "7") (pinfunction "IO3B_7") (pintype "bidirectional"))
      (node (ref "J11H") (pin "9") (pinfunction "9_9") (pintype "passive"))
      (node (ref "R13H") (pin "3") (pinfunction "R22_3") (pintype "passive"))
    )
    (net (code "75") (name "/RX0_TMDS0_P") (class "Default")
      (node (ref "D15H") (pin "5") (pinfunction "IO4A_5") (pintype "bidirectional"))
      (node (ref "D15H") (pin "6") (pinfunction "IO4B_6") (pintype "bidirectional"))
      (node (ref "J11H") (pin "7") (pinfunction "7_7") (pintype "passive"))
      (node (ref "R13H") (pin "4") (pinfunction "R12_4") (pintype "passive"))
    )
    (net (code "76") (name "/RX0_TMDS1_N") (class "Default")
      (node (ref "D16H") (pin "1") (pinfunction "IO1A_1") (pintype "bidirectional"))
      (node (ref "D16H") (pin "10") (pinfunction "IO1B_10") (pintype "bidirectional"))
      (node (ref "J11H") (pin "6") (pinfunction "6_6") (pintype "passive"))
      (node (ref "R12H") (pin "2") (pinfunction "R2_2") (pintype "passive"))
    )
    (net (code "77") (name "/RX0_TMDS1_P") (class "Default")
      (node (ref "D16H") (pin "2") (pinfunction "IO2A_2") (pintype "bidirectional"))
      (node (ref "D16H") (pin "9") (pinfunction "IO2B_9") (pintype "bidirectional"))
      (node (ref "J11H") (pin "4") (pinfunction "4_4") (pintype "passive"))
      (node (ref "R12H") (pin "1") (pinfunction "R1_1") (pintype "passive"))
    )
    (net (code "78") (name "/RX0_TMDS2_N") (class "Default")
      (node (ref "D16H") (pin "4") (pinfunction "IO3A_4") (pintype "bidirectional"))
      (node (ref "D16H") (pin "7") (pinfunction "IO3B_7") (pintype "bidirectional"))
      (node (ref "J11H") (pin "3") (pinfunction "3_3") (pintype "passive"))
      (node (ref "R11H") (pin "3") (pinfunction "R22_3") (pintype "passive"))
    )
    (net (code "79") (name "/RX0_TMDS2_P") (class "Default")
      (node (ref "D16H") (pin "5") (pinfunction "IO4A_5") (pintype "bidirectional"))
      (node (ref "D16H") (pin "6") (pinfunction "IO4B_6") (pintype "bidirectional"))
      (node (ref "J11H") (pin "1") (pinfunction "1_1") (pintype "passive"))
      (node (ref "R11H") (pin "4") (pinfunction "R12_4") (pintype "passive"))
    )
    (net (code "80") (name "/RX0_TMDS3_N") (class "Default")
      (node (ref "D15H") (pin "1") (pinfunction "IO1A_1") (pintype "bidirectional"))
      (node (ref "D15H") (pin "10") (pinfunction "IO1B_10") (pintype "bidirectional"))
      (node (ref "J11H") (pin "12") (pinfunction "12_12") (pintype "passive"))
      (node (ref "R14H") (pin "2") (pinfunction "R2_2") (pintype "passive"))
    )
    (net (code "81") (name "/RX0_TMDS3_P") (class "Default")
      (node (ref "D15H") (pin "2") (pinfunction "IO2A_2") (pintype "bidirectional"))
      (node (ref "D15H") (pin "9") (pinfunction "IO2B_9") (pintype "bidirectional"))
      (node (ref "J11H") (pin "10") (pinfunction "10_10") (pintype "passive"))
      (node (ref "R14H") (pin "1") (pinfunction "R1_1") (pintype "passive"))
    )
    (net (code "82") (name "/SMCLK") (class "Default")
      (node (ref "P13H") (pin "B5") (pinfunction "B5_B5") (pintype "passive"))
    )
    (net (code "83") (name "/SMDAT") (class "Default")
      (node (ref "P13H") (pin "B6") (pinfunction "B6_B6") (pintype "passive"))
    )
    (net (code "84") (name "/TX0_TMDS0_N") (class "Default")
      (node (ref "D11H") (pin "4") (pinfunction "IO3A_4") (pintype "bidirectional"))
      (node (ref "D11H") (pin "7") (pinfunction "IO3B_7") (pintype "bidirectional"))
      (node (ref "J10H") (pin "9") (pinfunction "9_9") (pintype "passive"))
    )
    (net (code "85") (name "/TX0_TMDS0_P") (class "Default")
      (node (ref "D11H") (pin "5") (pinfunction "IO4A_5") (pintype "bidirectional"))
      (node (ref "D11H") (pin "6") (pinfunction "IO4B_6") (pintype "bidirectional"))
      (node (ref "J10H") (pin "7") (pinfunction "7_7") (pintype "passive"))
    )
    (net (code "86") (name "/TX0_TMDS1_N") (class "Default")
      (node (ref "D12H") (pin "1") (pinfunction "IO1A_1") (pintype "bidirectional"))
      (node (ref "D12H") (pin "10") (pinfunction "IO1B_10") (pintype "bidirectional"))
      (node (ref "J10H") (pin "6") (pinfunction "6_6") (pintype "passive"))
    )
    (net (code "87") (name "/TX0_TMDS1_P") (class "Default")
      (node (ref "D12H") (pin "2") (pinfunction "IO2A_2") (pintype "bidirectional"))
      (node (ref "D12H") (pin "9") (pinfunction "IO2B_9") (pintype "bidirectional"))
      (node (ref "J10H") (pin "4") (pinfunction "4_4") (pintype "passive"))
    )
    (net (code "88") (name "/TX0_TMDS2_N") (class "Default")
      (node (ref "D12H") (pin "4") (pinfunction "IO3A_4") (pintype "bidirectional"))
      (node (ref "D12H") (pin "7") (pinfunction "IO3B_7") (pintype "bidirectional"))
      (node (ref "J10H") (pin "3") (pinfunction "3_3") (pintype "passive"))
    )
    (net (code "89") (name "/TX0_TMDS2_P") (class "Default")
      (node (ref "D12H") (pin "5") (pinfunction "IO4A_5") (pintype "bidirectional"))
      (node (ref "D12H") (pin "6") (pinfunction "IO4B_6") (pintype "bidirectional"))
      (node (ref "J10H") (pin "1") (pinfunction "1_1") (pintype "passive"))
    )
    (net (code "90") (name "/TX0_TMDS3_N") (class "Default")
      (node (ref "D11H") (pin "1") (pinfunction "IO1A_1") (pintype "bidirectional"))
      (node (ref "D11H") (pin "10") (pinfunction "IO1B_10") (pintype "bidirectional"))
      (node (ref "J10H") (pin "12") (pinfunction "12_12") (pintype "passive"))
    )
    (net (code "91") (name "/TX0_TMDS3_P") (class "Default")
      (node (ref "D11H") (pin "2") (pinfunction "IO2A_2") (pintype "bidirectional"))
      (node (ref "D11H") (pin "9") (pinfunction "IO2B_9") (pintype "bidirectional"))
      (node (ref "J10H") (pin "10") (pinfunction "10_10") (pintype "passive"))
    )
    (net (code "92") (name "/TX1_CEC") (class "Default")
      (node (ref "D21H") (pin "1") (pinfunction "IO1A_1") (pintype "bidirectional"))
      (node (ref "D21H") (pin "10") (pinfunction "IO1B_10") (pintype "bidirectional"))
      (node (ref "P10H") (pin "15") (pinfunction "CEC_15") (pintype "passive"))
    )
    (net (code "93") (name "/TX1_CLK_N") (class "Default")
      (node (ref "D22H") (pin "1") (pinfunction "IO1A_1") (pintype "bidirectional"))
      (node (ref "D22H") (pin "10") (pinfunction "IO1B_10") (pintype "bidirectional"))
      (node (ref "P10H") (pin "14") (pinfunction "TMDS_CK-_14") (pintype "passive"))
    )
    (net (code "94") (name "/TX1_CLK_P") (class "Default")
      (node (ref "D22H") (pin "2") (pinfunction "IO2A_2") (pintype "bidirectional"))
      (node (ref "D22H") (pin "9") (pinfunction "IO2B_9") (pintype "bidirectional"))
      (node (ref "P10H") (pin "12") (pinfunction "TMDS_CK+_12") (pintype "passive"))
    )
    (net (code "95") (name "/TX1_HDMI_5V") (class "Default")
      (node (ref "D20H") (pin "1") (pinfunction "K_1") (pintype "passive"))
      (node (ref "F11H") (pin "2") (pinfunction "2_2") (pintype "bidirectional"))
      (node (ref "P10H") (pin "19") (pinfunction "+5V_19") (pintype "passive"))
    )
    (net (code "96") (name "/TX1_HPD") (class "Default")
      (node (ref "D21H") (pin "5") (pinfunction "IO4A_5") (pintype "bidirectional"))
      (node (ref "D21H") (pin "6") (pinfunction "IO4B_6") (pintype "bidirectional"))
      (node (ref "P10H") (pin "1") (pinfunction "HPD_1") (pintype "passive"))
      (node (ref "R40H") (pin "2") (pinfunction "2_2") (pintype "passive"))
      (node (ref "U10H") (pin "1") (pinfunction "A_1") (pintype "input"))
    )
    (net (code "97") (name "/TX1_HPD_LL") (class "Default")
      (node (ref "U10H") (pin "2") (pinfunction "~{O}_2") (pintype "output"))
    )
    (net (code "98") (name "/TX1_SCL") (class "Default")
      (node (ref "D21H") (pin "2") (pinfunction "IO2A_2") (pintype "bidirectional"))
      (node (ref "D21H") (pin "9") (pinfunction "IO2B_9") (pintype "bidirectional"))
      (node (ref "P10H") (pin "17") (pinfunction "SCL_17") (pintype "open_collector"))
      (node (ref "Q18H") (pin "3") (pinfunction "D_3") (pintype "passive"))
      (node (ref "R43H") (pin "2") (pinfunction "2_2") (pintype "passive"))
    )
    (net (code "99") (name "/TX1_SCL_LV") (class "Default")
      (node (ref "Q18H") (pin "2") (pinfunction "S_2") (pintype "passive"))
      (node (ref "R44H") (pin "2") (pinfunction "2_2") (pintype "passive"))
    )
    (net (code "100") (name "/TX1_SDA") (class "Default")
      (node (ref "D21H") (pin "4") (pinfunction "IO3A_4") (pintype "bidirectional"))
      (node (ref "D21H") (pin "7") (pinfunction "IO3B_7") (pintype "bidirectional"))
      (node (ref "P10H") (pin "18") (pinfunction "SDA_18") (pintype "open_collector"))
      (node (ref "Q17H") (pin "3") (pinfunction "D_3") (pintype "passive"))
      (node (ref "R41H") (pin "2") (pinfunction "2_2") (pintype "passive"))
    )
    (net (code "101") (name "/TX1_SDA_LV") (class "Default")
      (node (ref "Q17H") (pin "2") (pinfunction "S_2") (pintype "passive"))
      (node (ref "R42H") (pin "2") (pinfunction "2_2") (pintype "passive"))
    )
    (net (code "102") (name "/TX1_TMDS0_N") (class "Default")
      (node (ref "D22H") (pin "4") (pinfunction "IO3A_4") (pintype "bidirectional"))
      (node (ref "D22H") (pin "7") (pinfunction "IO3B_7") (pintype "bidirectional"))
      (node (ref "P10H") (pin "11") (pinfunction "TMDS0-_11") (pintype "passive"))
    )
    (net (code "103") (name "/TX1_TMDS0_P") (class "Default")
      (node (ref "D22H") (pin "5") (pinfunction "IO4A_5") (pintype "bidirectional"))
      (node (ref "D22H") (pin "6") (pinfunction "IO4B_6") (pintype "bidirectional"))
      (node (ref "P10H") (pin "9") (pinfunction "TMDS0+_9") (pintype "passive"))
    )
    (net (code "104") (name "/TX1_TMDS1_N") (class "Default")
      (node (ref "D23H") (pin "1") (pinfunction "IO1A_1") (pintype "bidirectional"))
      (node (ref "D23H") (pin "10") (pinfunction "IO1B_10") (pintype "bidirectional"))
      (node (ref "P10H") (pin "8") (pinfunction "TMDS1-_8") (pintype "passive"))
    )
    (net (code "105") (name "/TX1_TMDS1_P") (class "Default")
      (node (ref "D23H") (pin "2") (pinfunction "IO2A_2") (pintype "bidirectional"))
      (node (ref "D23H") (pin "9") (pinfunction "IO2B_9") (pintype "bidirectional"))
      (node (ref "P10H") (pin "6") (pinfunction "TMDS1+_6") (pintype "passive"))
    )
    (net (code "106") (name "/TX1_TMDS2_N") (class "Default")
      (node (ref "D23H") (pin "4") (pinfunction "IO3A_4") (pintype "bidirectional"))
      (node (ref "D23H") (pin "7") (pinfunction "IO3B_7") (pintype "bidirectional"))
      (node (ref "P10H") (pin "5") (pinfunction "TMDS2-_5") (pintype "passive"))
    )
    (net (code "107") (name "/TX1_TMDS2_P") (class "Default")
      (node (ref "D23H") (pin "5") (pinfunction "IO4A_5") (pintype "bidirectional"))
      (node (ref "D23H") (pin "6") (pinfunction "IO4B_6") (pintype "bidirectional"))
      (node (ref "P10H") (pin "3") (pinfunction "TMDS2+_3") (pintype "passive"))
    )
    (net (code "108") (name "/TX_HDMI_5V") (class "Default")
      (node (ref "D13H") (pin "1") (pinfunction "K_1") (pintype "passive"))
      (node (ref "F10H") (pin "2") (pinfunction "2_2") (pintype "bidirectional"))
      (node (ref "J10H") (pin "18") (pinfunction "18_18") (pintype "passive"))
      (node (ref "Q13H") (pin "2") (pinfunction "S_2") (pintype "passive"))
      (node (ref "R27H") (pin "1") (pinfunction "1_1") (pintype "passive"))
    )
    (net (code "109") (name "/WAKE#") (class "Default")
      (node (ref "P13H") (pin "B11") (pinfunction "B11_B11") (pintype "passive"))
    )
    (net (code "110") (name "GND") (class "Default")
      (node (ref "C10H") (pin "2") (pinfunction "2_2") (pintype "passive"))
      (node (ref "C11H") (pin "2") (pinfunction "2_2") (pintype "passive"))
      (node (ref "C12H") (pin "2") (pinfunction "2_2") (pintype "passive"))
      (node (ref "D10H") (pin "3") (pinfunction "GND1_3") (pintype "input"))
      (node (ref "D11H") (pin "3") (pinfunction "GND1_3") (pintype "input"))
      (node (ref "D12H") (pin "3") (pinfunction "GND1_3") (pintype "input"))
      (node (ref "D13H") (pin "2") (pinfunction "A_2") (pintype "passive"))
      (node (ref "D14H") (pin "3") (pinfunction "GND1_3") (pintype "input"))
      (node (ref "D15H") (pin "3") (pinfunction "GND1_3") (pintype "input"))
      (node (ref "D16H") (pin "3") (pinfunction "GND1_3") (pintype "input"))
      (node (ref "D17H") (pin "3") (pinfunction "GND1_3") (pintype "input"))
      (node (ref "D18H") (pin "3") (pinfunction "GND1_3") (pintype "input"))
      (node (ref "D19H") (pin "3") (pinfunction "GND1_3") (pintype "input"))
      (node (ref "D20H") (pin "2") (pinfunction "A_2") (pintype "passive"))
      (node (ref "D21H") (pin "3") (pinfunction "GND1_3") (pintype "input"))
      (node (ref "D22H") (pin "3") (pinfunction "GND1_3") (pintype "input"))
      (node (ref "D23H") (pin "3") (pinfunction "GND1_3") (pintype "input"))
      (node (ref "J10H") (pin "0") (pinfunction "GND_0") (pintype "passive"))
      (node (ref "J10H") (pin "11") (pinfunction "11_11") (pintype "passive"))
      (node (ref "J10H") (pin "17") (pinfunction "17_17") (pintype "passive"))
      (node (ref "J10H") (pin "2") (pinfunction "2_2") (pintype "passive"))
      (node (ref "J10H") (pin "5") (pinfunction "5_5") (pintype "passive"))
      (node (ref "J10H") (pin "8") (pinfunction "8_8") (pintype "passive"))
      (node (ref "J11H") (pin "0") (pinfunction "GND_0") (pintype "passive"))
      (node (ref "J11H") (pin "11") (pinfunction "11_11") (pintype "passive"))
      (node (ref "J11H") (pin "17") (pinfunction "17_17") (pintype "passive"))
      (node (ref "J11H") (pin "2") (pinfunction "2_2") (pintype "passive"))
      (node (ref "J11H") (pin "5") (pinfunction "5_5") (pintype "passive"))
      (node (ref "J11H") (pin "8") (pinfunction "8_8") (pintype "passive"))
      (node (ref "J12H") (pin "0") (pinfunction "GND_0") (pintype "passive"))
      (node (ref "J12H") (pin "11") (pinfunction "11_11") (pintype "passive"))
      (node (ref "J12H") (pin "17") (pinfunction "17_17") (pintype "passive"))
      (node (ref "J12H") (pin "2") (pinfunction "2_2") (pintype "passive"))
      (node (ref "J12H") (pin "5") (pinfunction "5_5") (pintype "passive"))
      (node (ref "J12H") (pin "8") (pinfunction "8_8") (pintype "passive"))
      (node (ref "P10H") (pin "0") (pinfunction "SHELL_0") (pintype "passive"))
      (node (ref "P10H") (pin "10") (pinfunction "Shield_10") (pintype "power_in"))
      (node (ref "P10H") (pin "13") (pinfunction "Shield_13") (pintype "power_in"))
      (node (ref "P10H") (pin "16") (pinfunction "GND_16") (pintype "power_in"))
      (node (ref "P10H") (pin "4") (pinfunction "Shield_4") (pintype "power_in"))
      (node (ref "P10H") (pin "7") (pinfunction "Shield_7") (pintype "power_in"))
      (node (ref "P11H") (pin "11") (pinfunction "11_11") (pintype "passive"))
      (node (ref "P11H") (pin "12") (pinfunction "12_12") (pintype "passive"))
      (node (ref "P11H") (pin "21") (pinfunction "21_21") (pintype "passive"))
      (node (ref "P11H") (pin "22") (pinfunction "22_22") (pintype "passive"))
      (node (ref "P12H") (pin "0") (pinfunction "PAD_0") (pintype "passive"))
      (node (ref "P12H") (pin "5") (pinfunction "GND_5") (pintype "passive"))
      (node (ref "P13H") (pin "A12") (pinfunction "A12_A12") (pintype "passive"))
      (node (ref "P13H") (pin "A15") (pinfunction "A15_A15") (pintype "passive"))
      (node (ref "P13H") (pin "A18") (pinfunction "A18_A18") (pintype "passive"))
      (node (ref "P13H") (pin "A20") (pinfunction "A20_A20") (pintype "passive"))
      (node (ref "P13H") (pin "A23") (pinfunction "A23_A23") (pintype "passive"))
      (node (ref "P13H") (pin "A24") (pinfunction "A24_A24") (pintype "passive"))
      (node (ref "P13H") (pin "A27") (pinfunction "A27_A27") (pintype "passive"))
      (node (ref "P13H") (pin "A28") (pinfunction "A28_A28") (pintype "passive"))
      (node (ref "P13H") (pin "A31") (pinfunction "A31_A31") (pintype "passive"))
      (node (ref "P13H") (pin "A4") (pinfunction "A4_A4") (pintype "passive"))
      (node (ref "P13H") (pin "B13") (pinfunction "B13_B13") (pintype "passive"))
      (node (ref "P13H") (pin "B16") (pinfunction "B16_B16") (pintype "passive"))
      (node (ref "P13H") (pin "B18") (pinfunction "B18_B18") (pintype "passive"))
      (node (ref "P13H") (pin "B21") (pinfunction "B21_B21") (pintype "passive"))
      (node (ref "P13H") (pin "B22") (pinfunction "B22_B22") (pintype "passive"))
      (node (ref "P13H") (pin "B25") (pinfunction "B25_B25") (pintype "passive"))
      (node (ref "P13H") (pin "B26") (pinfunction "B26_B26") (pintype "passive"))
      (node (ref "P13H") (pin "B29") (pinfunction "B29_B29") (pintype "passive"))
      (node (ref "P13H") (pin "B32") (pinfunction "B32_B32") (pintype "passive"))
      (node (ref "P13H") (pin "B4") (pinfunction "B4_B4") (pintype "passive"))
      (node (ref "P13H") (pin "B7") (pinfunction "B7_B7") (pintype "passive"))
      (node (ref "Q11H") (pin "2") (pinfunction "S_2") (pintype "passive"))
      (node (ref "Q12H") (pin "2") (pinfunction "S_2") (pintype "passive"))
      (node (ref "Q14H") (pin "2") (pinfunction "S_2") (pintype "passive"))
      (node (ref "Q15H") (pin "2") (pinfunction "S_2") (pintype "passive"))
      (node (ref "R10H") (pin "1") (pinfunction "1_1") (pintype "passive"))
      (node (ref "R17H") (pin "2") (pinfunction "2_2") (pintype "passive"))
      (node (ref "R20H") (pin "2") (pinfunction "2_2") (pintype "passive"))
      (node (ref "R31H") (pin "2") (pinfunction "2_2") (pintype "passive"))
      (node (ref "R33H") (pin "2") (pinfunction "2_2") (pintype "passive"))
      (node (ref "R34H") (pin "2") (pinfunction "2_2") (pintype "passive"))
      (node (ref "R39H") (pin "2") (pinfunction "2_2") (pintype "passive"))
      (node (ref "R40H") (pin "1") (pinfunction "1_1") (pintype "passive"))
      (node (ref "TP11H") (pin "1") (pinfunction "1_1") (pintype "passive"))
      (node (ref "TP13H") (pin "1") (pinfunction "1_1") (pintype "passive"))
      (node (ref "U10H") (pin "7") (pinfunction "GND_7") (pintype "power_in"))
    )
    (net (code "111") (name "Net-(P12H-ID)") (class "Default")
      (node (ref "P12H") (pin "4") (pinfunction "ID_4") (pintype "passive"))
      (node (ref "R39H") (pin "1") (pinfunction "1_1") (pintype "passive"))
    )
    (net (code "112") (name "Net-(Q10H-G)") (class "Default")
      (node (ref "Q10H") (pin "1") (pinfunction "G_1") (pintype "passive"))
      (node (ref "Q11H") (pin "3") (pinfunction "D_3") (pintype "passive"))
      (node (ref "R16H") (pin "2") (pinfunction "2_2") (pintype "passive"))
    )
    (net (code "113") (name "Net-(Q12H-D)") (class "Default")
      (node (ref "Q12H") (pin "3") (pinfunction "D_3") (pintype "passive"))
      (node (ref "R18H") (pin "1") (pinfunction "1_1") (pintype "passive"))
    )
    (net (code "114") (name "Net-(Q13H-D)") (class "Default")
      (node (ref "Q13H") (pin "3") (pinfunction "D_3") (pintype "passive"))
      (node (ref "R32H") (pin "2") (pinfunction "2_2") (pintype "passive"))
    )
    (net (code "115") (name "Net-(Q13H-G)") (class "Default")
      (node (ref "Q13H") (pin "1") (pinfunction "G_1") (pintype "passive"))
      (node (ref "Q14H") (pin "3") (pinfunction "D_3") (pintype "passive"))
      (node (ref "R27H") (pin "2") (pinfunction "2_2") (pintype "passive"))
    )
    (net (code "116") (name "P3.3V") (class "Default")
      (node (ref "C10H") (pin "1") (pinfunction "1_1") (pintype "passive"))
      (node (ref "C12H") (pin "1") (pinfunction "1_1") (pintype "passive"))
      (node (ref "P11H") (pin "1") (pinfunction "1_1") (pintype "passive"))
      (node (ref "P11H") (pin "2") (pinfunction "2_2") (pintype "passive"))
      (node (ref "Q16H") (pin "1") (pinfunction "G_1") (pintype "passive"))
      (node (ref "Q17H") (pin "1") (pinfunction "G_1") (pintype "passive"))
      (node (ref "Q18H") (pin "1") (pinfunction "G_1") (pintype "passive"))
      (node (ref "R11H") (pin "1") (pinfunction "R1_1") (pintype "passive"))
      (node (ref "R11H") (pin "2") (pinfunction "R2_2") (pintype "passive"))
      (node (ref "R12H") (pin "3") (pinfunction "R22_3") (pintype "passive"))
      (node (ref "R12H") (pin "4") (pinfunction "R12_4") (pintype "passive"))
      (node (ref "R13H") (pin "1") (pinfunction "R1_1") (pintype "passive"))
      (node (ref "R13H") (pin "2") (pinfunction "R2_2") (pintype "passive"))
      (node (ref "R14H") (pin "3") (pinfunction "R22_3") (pintype "passive"))
      (node (ref "R14H") (pin "4") (pinfunction "R12_4") (pintype "passive"))
      (node (ref "R19H") (pin "3") (pinfunction "R22_3") (pintype "passive"))
      (node (ref "R19H") (pin "4") (pinfunction "R12_4") (pintype "passive"))
      (node (ref "R21H") (pin "1") (pinfunction "R1_1") (pintype "passive"))
      (node (ref "R21H") (pin "2") (pinfunction "R2_2") (pintype "passive"))
      (node (ref "R22H") (pin "1") (pinfunction "R1_1") (pintype "passive"))
      (node (ref "R22H") (pin "2") (pinfunction "R2_2") (pintype "passive"))
      (node (ref "R23H") (pin "1") (pinfunction "1_1") (pintype "passive"))
      (node (ref "R24H") (pin "1") (pinfunction "1_1") (pintype "passive"))
      (node (ref "R25H") (pin "3") (pinfunction "R22_3") (pintype "passive"))
      (node (ref "R25H") (pin "4") (pinfunction "R12_4") (pintype "passive"))
      (node (ref "R36H") (pin "1") (pinfunction "1_1") (pintype "passive"))
      (node (ref "R42H") (pin "1") (pinfunction "1_1") (pintype "passive"))
      (node (ref "R44H") (pin "1") (pinfunction "1_1") (pintype "passive"))
      (node (ref "U10H") (pin "14") (pinfunction "VCC_14") (pintype "power_in"))
    )
    (net (code "117") (name "P5.0V") (class "Default")
      (node (ref "F10H") (pin "1") (pinfunction "1_1") (pintype "bidirectional"))
      (node (ref "F11H") (pin "1") (pinfunction "1_1") (pintype "bidirectional"))
      (node (ref "Q10H") (pin "2") (pinfunction "S_2") (pintype "passive"))
      (node (ref "R16H") (pin "1") (pinfunction "1_1") (pintype "passive"))
      (node (ref "R41H") (pin "1") (pinfunction "1_1") (pintype "passive"))
      (node (ref "R43H") (pin "1") (pinfunction "1_1") (pintype "passive"))
    )
    (net (code "118") (name "P12V") (class "Default")
      (node (ref "P13H") (pin "A2") (pinfunction "A2_A2") (pintype "passive"))
      (node (ref "P13H") (pin "A3") (pinfunction "A3_A3") (pintype "passive"))
      (node (ref "P13H") (pin "B1") (pinfunction "B1_B1") (pintype "passive"))
      (node (ref "P13H") (pin "B2") (pinfunction "B2_B2") (pintype "passive"))
      (node (ref "P13H") (pin "B3") (pinfunction "B3_B3") (pintype "passive"))
    )
    (net (code "119") (name "VUSB") (class "Default")
      (node (ref "C11H") (pin "1") (pinfunction "1_1") (pintype "passive"))
      (node (ref "P12H") (pin "1") (pinfunction "VBUS_1") (pintype "passive"))
    )
    (net (code "120") (name "unconnected-(J10H-Pad14)") (class "Default")
      (node (ref "J10H") (pin "14") (pinfunction "14_14") (pintype "passive"))
    )
    (net (code "121") (name "unconnected-(J11H-Pad14)") (class "Default")
      (node (ref "J11H") (pin "14") (pinfunction "14_14") (pintype "passive"))
    )
    (net (code "122") (name "unconnected-(J11H-Pad18)") (class "Default")
      (node (ref "J11H") (pin "18") (pinfunction "18_18") (pintype "passive"))
    )
    (net (code "123") (name "unconnected-(J12H-Pad14)") (class "Default")
      (node (ref "J12H") (pin "14") (pinfunction "14_14") (pintype "passive"))
    )
    (net (code "124") (name "unconnected-(P10H-Utility-Pad2)") (class "Default")
      (node (ref "P10H") (pin "2") (pinfunction "Utility_2") (pintype "passive+no_connect"))
    )
    (net (code "125") (name "unconnected-(P13H-PadA5)") (class "Default")
      (node (ref "P13H") (pin "A5") (pinfunction "A5_A5") (pintype "passive"))
    )
    (net (code "126") (name "unconnected-(P13H-PadA6)") (class "Default")
      (node (ref "P13H") (pin "A6") (pinfunction "A6_A6") (pintype "passive"))
    )
    (net (code "127") (name "unconnected-(P13H-PadA7)") (class "Default")
      (node (ref "P13H") (pin "A7") (pinfunction "A7_A7") (pintype "passive"))
    )
    (net (code "128") (name "unconnected-(P13H-PadA8)") (class "Default")
      (node (ref "P13H") (pin "A8") (pinfunction "A8_A8") (pintype "passive"))
    )
    (net (code "129") (name "unconnected-(P13H-PadA9)") (class "Default")
      (node (ref "P13H") (pin "A9") (pinfunction "A9_A9") (pintype "passive"))
    )
    (net (code "130") (name "unconnected-(P13H-PadA10)") (class "Default")
      (node (ref "P13H") (pin "A10") (pinfunction "A10_A10") (pintype "passive"))
    )
    (net (code "131") (name "unconnected-(P13H-PadA19)") (class "Default")
      (node (ref "P13H") (pin "A19") (pinfunction "A19_A19") (pintype "passive+no_connect"))
    )
    (net (code "132") (name "unconnected-(P13H-PadA32)") (class "Default")
      (node (ref "P13H") (pin "A32") (pinfunction "A32_A32") (pintype "passive"))
    )
    (net (code "133") (name "unconnected-(P13H-PadB8)") (class "Default")
      (node (ref "P13H") (pin "B8") (pinfunction "B8_B8") (pintype "passive"))
    )
    (net (code "134") (name "unconnected-(P13H-PadB9)") (class "Default")
      (node (ref "P13H") (pin "B9") (pinfunction "B9_B9") (pintype "passive"))
    )
    (net (code "135") (name "unconnected-(P13H-PadB10)") (class "Default")
      (node (ref "P13H") (pin "B10") (pinfunction "B10_B10") (pintype "passive"))
    )
    (net (code "136") (name "unconnected-(P13H-PadB12)") (class "Default")
      (node (ref "P13H") (pin "B12") (pinfunction "B12_B12") (pintype "passive"))
    )
    (net (code "137") (name "unconnected-(P13H-PadB30)") (class "Default")
      (node (ref "P13H") (pin "B30") (pinfunction "B30_B30") (pintype "passive"))
    )
  )
)
